# SCH_Robo_2025-09-25.net
KiCad netlist of a schematic drawn in EasyEDA
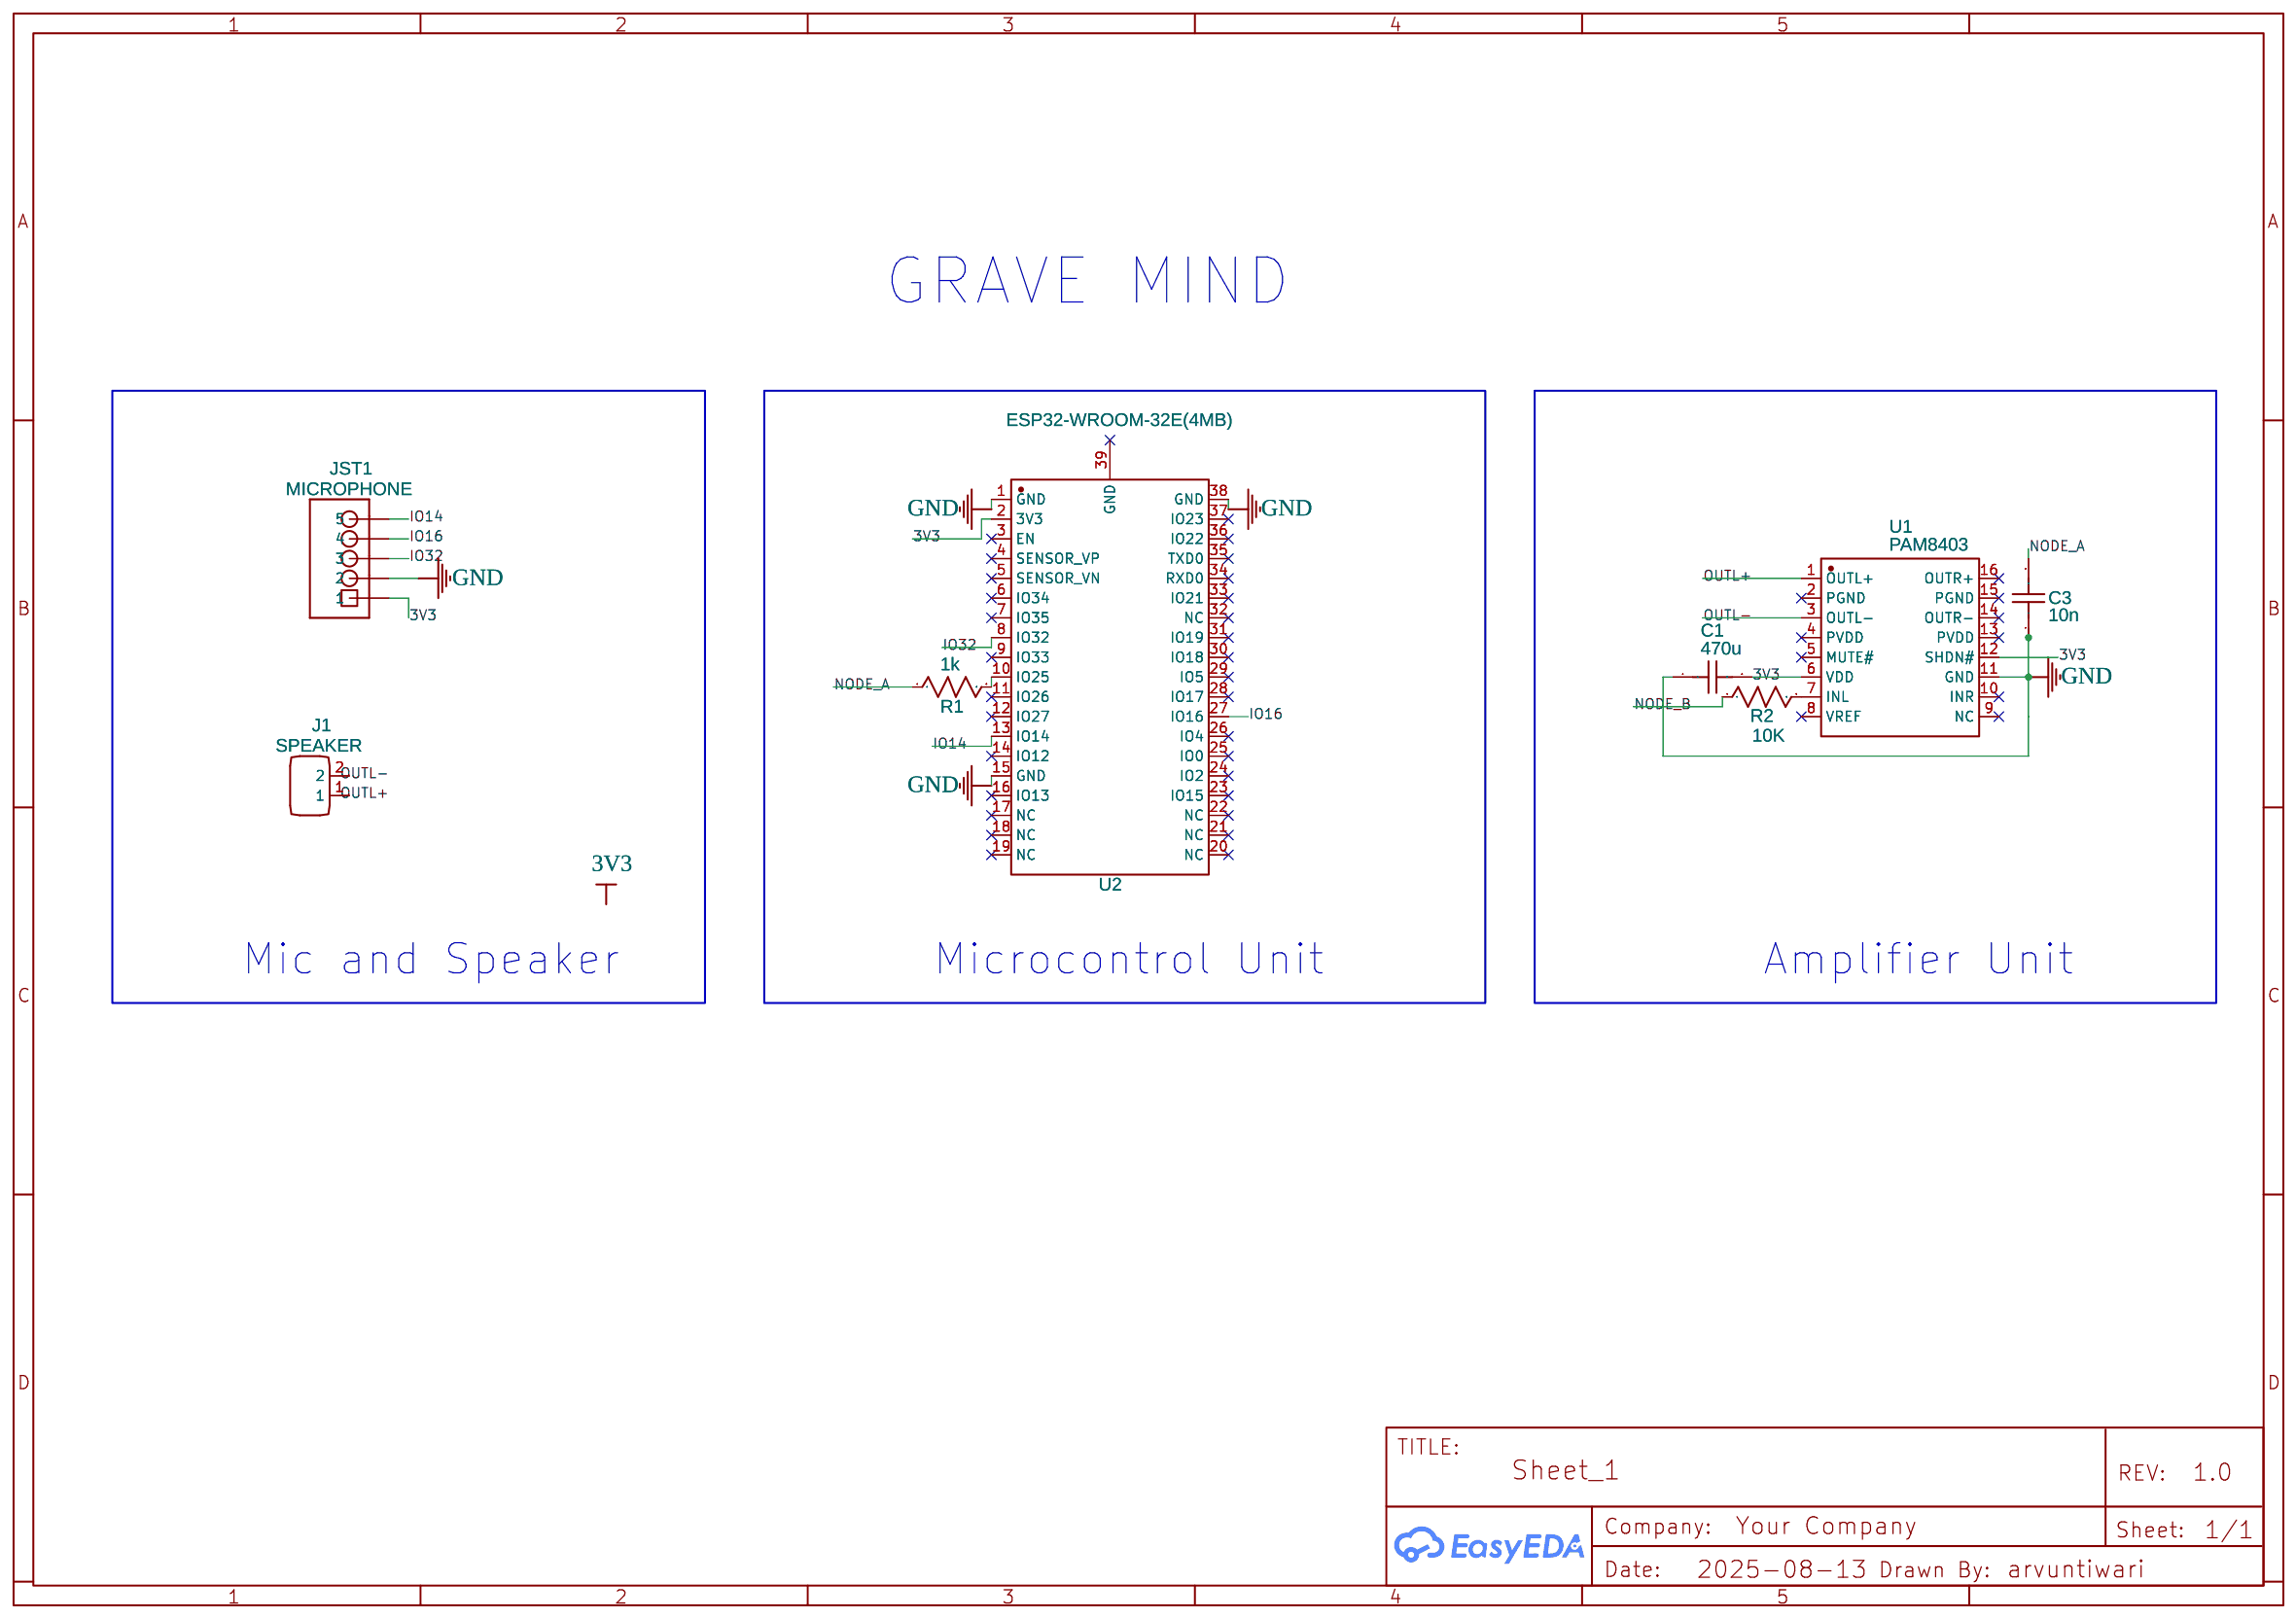
[diagram p0: schematic sheet]

(export (version "E")
  (design (tool "Eeschema 10.0.6"))
  (components
    (comp (ref "C1") (value "470u") (libsource (lib "") (part "C_0603_US_1")))
    (comp (ref "C3") (value "10n") (libsource (lib "") (part "C_0603_US")))
    (comp (ref "J1") (value "SPEAKER") (libsource (lib "") (part "JST 2pin Female")))
    (comp (ref "JST1") (value "MICROPHONE") (libsource (lib "") (part "JST_5-PIN_Female_Connector")))
    (comp (ref "R1") (value "1k") (libsource (lib "") (part "R_0603_US")))
    (comp (ref "R2") (value "10K") (libsource (lib "") (part "R_0603_US")))
    (comp (ref "U1")
      (value "PAM8403")
      (fields (field (name "Manufacturer") "Slkor(萨科微)"))
      (libsource (lib "") (part "PAM8403"))
    )
    (comp (ref "U2")
      (value "ESP32-WROOM-32E(4MB)")
      (fields
        (field (name "Manufacturer Part") "ESP32-WROOM-32E-N4")
        (field (name "Manufacturer") "ESPRESSIF(乐鑫)")
      )
      (libsource (lib "") (part "ESP32-WROOM-32E(4MB)"))
    )
  )
  (nets
    (net (code "1") (name "/IO14") (class "Default")
      (node (ref "JST1") (pin "5") (pinfunction "5_5") (pintype "unspecified"))
      (node (ref "U2") (pin "13") (pinfunction "IO14_13") (pintype "unspecified"))
    )
    (net (code "2") (name "/IO16") (class "Default")
      (node (ref "JST1") (pin "4") (pinfunction "4_4") (pintype "unspecified"))
      (node (ref "U2") (pin "27") (pinfunction "IO16_27") (pintype "unspecified"))
    )
    (net (code "3") (name "/IO32") (class "Default")
      (node (ref "JST1") (pin "3") (pinfunction "3_3") (pintype "unspecified"))
      (node (ref "U2") (pin "8") (pinfunction "IO32_8") (pintype "unspecified"))
    )
    (net (code "4") (name "/NODE_A") (class "Default")
      (node (ref "C3") (pin "2") (pinfunction "2_2") (pintype "unspecified"))
      (node (ref "R1") (pin "1") (pinfunction "1_1") (pintype "unspecified"))
    )
    (net (code "5") (name "/NODE_B") (class "Default")
      (node (ref "R2") (pin "1") (pinfunction "1_1") (pintype "unspecified"))
    )
    (net (code "6") (name "/OUTL+") (class "Default")
      (node (ref "J1") (pin "1") (pinfunction "1_1") (pintype "unspecified"))
      (node (ref "U1") (pin "1") (pinfunction "OUTL+_1") (pintype "unspecified"))
    )
    (net (code "7") (name "/OUTL-") (class "Default")
      (node (ref "J1") (pin "2") (pinfunction "2_2") (pintype "unspecified"))
      (node (ref "U1") (pin "3") (pinfunction "OUTL-_3") (pintype "unspecified"))
    )
    (net (code "8") (name "3V3") (class "Default")
      (node (ref "C1") (pin "2") (pinfunction "2_2") (pintype "unspecified"))
      (node (ref "JST1") (pin "1") (pinfunction "1_1") (pintype "unspecified"))
      (node (ref "U1") (pin "12") (pinfunction "SHDN#_12") (pintype "unspecified"))
      (node (ref "U1") (pin "6") (pinfunction "VDD_6") (pintype "unspecified"))
      (node (ref "U2") (pin "2") (pinfunction "3V3_2") (pintype "unspecified"))
    )
    (net (code "9") (name "GND") (class "Default")
      (node (ref "C1") (pin "1") (pinfunction "1_1") (pintype "unspecified"))
      (node (ref "C3") (pin "1") (pinfunction "1_1") (pintype "unspecified"))
      (node (ref "JST1") (pin "2") (pinfunction "2_2") (pintype "unspecified"))
      (node (ref "U1") (pin "11") (pinfunction "GND_11") (pintype "unspecified"))
      (node (ref "U2") (pin "1") (pinfunction "GND_1") (pintype "unspecified"))
      (node (ref "U2") (pin "15") (pinfunction "GND_15") (pintype "unspecified"))
      (node (ref "U2") (pin "38") (pinfunction "GND_38") (pintype "unspecified"))
    )
    (net (code "10") (name "Net-(U1-INL)") (class "Default")
      (node (ref "R2") (pin "2") (pinfunction "2_2") (pintype "unspecified"))
      (node (ref "U1") (pin "7") (pinfunction "INL_7") (pintype "unspecified"))
    )
    (net (code "11") (name "Net-(U2-IO25)") (class "Default")
      (node (ref "R1") (pin "2") (pinfunction "2_2") (pintype "unspecified"))
      (node (ref "U2") (pin "10") (pinfunction "IO25_10") (pintype "unspecified"))
    )
    (net (code "12") (name "unconnected-(U1-INR-Pad10)") (class "Default")
      (node (ref "U1") (pin "10") (pinfunction "INR_10") (pintype "unspecified+no_connect"))
    )
    (net (code "13") (name "unconnected-(U1-MUTE#-Pad5)") (class "Default")
      (node (ref "U1") (pin "5") (pinfunction "MUTE#_5") (pintype "unspecified+no_connect"))
    )
    (net (code "14") (name "unconnected-(U1-NC-Pad9)") (class "Default")
      (node (ref "U1") (pin "9") (pinfunction "NC_9") (pintype "unspecified+no_connect"))
    )
    (net (code "15") (name "unconnected-(U1-OUTR+-Pad16)") (class "Default")
      (node (ref "U1") (pin "16") (pinfunction "OUTR+_16") (pintype "unspecified+no_connect"))
    )
    (net (code "16") (name "unconnected-(U1-OUTR--Pad14)") (class "Default")
      (node (ref "U1") (pin "14") (pinfunction "OUTR-_14") (pintype "unspecified+no_connect"))
    )
    (net (code "17") (name "unconnected-(U1-PGND-Pad2)") (class "Default")
      (node (ref "U1") (pin "2") (pinfunction "PGND_2") (pintype "unspecified+no_connect"))
    )
    (net (code "18") (name "unconnected-(U1-PGND-Pad15)") (class "Default")
      (node (ref "U1") (pin "15") (pinfunction "PGND_15") (pintype "unspecified+no_connect"))
    )
    (net (code "19") (name "unconnected-(U1-PVDD-Pad4)") (class "Default")
      (node (ref "U1") (pin "4") (pinfunction "PVDD_4") (pintype "unspecified+no_connect"))
    )
    (net (code "20") (name "unconnected-(U1-PVDD-Pad13)") (class "Default")
      (node (ref "U1") (pin "13") (pinfunction "PVDD_13") (pintype "unspecified+no_connect"))
    )
    (net (code "21") (name "unconnected-(U1-VREF-Pad8)") (class "Default")
      (node (ref "U1") (pin "8") (pinfunction "VREF_8") (pintype "unspecified+no_connect"))
    )
    (net (code "22") (name "unconnected-(U2-EN-Pad3)") (class "Default")
      (node (ref "U2") (pin "3") (pinfunction "EN_3") (pintype "unspecified+no_connect"))
    )
    (net (code "23") (name "unconnected-(U2-GND-Pad39)") (class "Default")
      (node (ref "U2") (pin "39") (pinfunction "GND_39") (pintype "unspecified+no_connect"))
    )
    (net (code "24") (name "unconnected-(U2-IO0-Pad25)") (class "Default")
      (node (ref "U2") (pin "25") (pinfunction "IO0_25") (pintype "unspecified+no_connect"))
    )
    (net (code "25") (name "unconnected-(U2-IO2-Pad24)") (class "Default")
      (node (ref "U2") (pin "24") (pinfunction "IO2_24") (pintype "unspecified+no_connect"))
    )
    (net (code "26") (name "unconnected-(U2-IO4-Pad26)") (class "Default")
      (node (ref "U2") (pin "26") (pinfunction "IO4_26") (pintype "unspecified+no_connect"))
    )
    (net (code "27") (name "unconnected-(U2-IO5-Pad29)") (class "Default")
      (node (ref "U2") (pin "29") (pinfunction "IO5_29") (pintype "unspecified+no_connect"))
    )
    (net (code "28") (name "unconnected-(U2-IO12-Pad14)") (class "Default")
      (node (ref "U2") (pin "14") (pinfunction "IO12_14") (pintype "unspecified+no_connect"))
    )
    (net (code "29") (name "unconnected-(U2-IO13-Pad16)") (class "Default")
      (node (ref "U2") (pin "16") (pinfunction "IO13_16") (pintype "unspecified+no_connect"))
    )
    (net (code "30") (name "unconnected-(U2-IO15-Pad23)") (class "Default")
      (node (ref "U2") (pin "23") (pinfunction "IO15_23") (pintype "unspecified+no_connect"))
    )
    (net (code "31") (name "unconnected-(U2-IO17-Pad28)") (class "Default")
      (node (ref "U2") (pin "28") (pinfunction "IO17_28") (pintype "unspecified+no_connect"))
    )
    (net (code "32") (name "unconnected-(U2-IO18-Pad30)") (class "Default")
      (node (ref "U2") (pin "30") (pinfunction "IO18_30") (pintype "unspecified+no_connect"))
    )
    (net (code "33") (name "unconnected-(U2-IO19-Pad31)") (class "Default")
      (node (ref "U2") (pin "31") (pinfunction "IO19_31") (pintype "unspecified+no_connect"))
    )
    (net (code "34") (name "unconnected-(U2-IO21-Pad33)") (class "Default")
      (node (ref "U2") (pin "33") (pinfunction "IO21_33") (pintype "unspecified+no_connect"))
    )
    (net (code "35") (name "unconnected-(U2-IO22-Pad36)") (class "Default")
      (node (ref "U2") (pin "36") (pinfunction "IO22_36") (pintype "unspecified+no_connect"))
    )
    (net (code "36") (name "unconnected-(U2-IO23-Pad37)") (class "Default")
      (node (ref "U2") (pin "37") (pinfunction "IO23_37") (pintype "unspecified+no_connect"))
    )
    (net (code "37") (name "unconnected-(U2-IO26-Pad11)") (class "Default")
      (node (ref "U2") (pin "11") (pinfunction "IO26_11") (pintype "unspecified+no_connect"))
    )
    (net (code "38") (name "unconnected-(U2-IO27-Pad12)") (class "Default")
      (node (ref "U2") (pin "12") (pinfunction "IO27_12") (pintype "unspecified+no_connect"))
    )
    (net (code "39") (name "unconnected-(U2-IO33-Pad9)") (class "Default")
      (node (ref "U2") (pin "9") (pinfunction "IO33_9") (pintype "unspecified+no_connect"))
    )
    (net (code "40") (name "unconnected-(U2-IO34-Pad6)") (class "Default")
      (node (ref "U2") (pin "6") (pinfunction "IO34_6") (pintype "unspecified+no_connect"))
    )
    (net (code "41") (name "unconnected-(U2-IO35-Pad7)") (class "Default")
      (node (ref "U2") (pin "7") (pinfunction "IO35_7") (pintype "unspecified+no_connect"))
    )
    (net (code "42") (name "unconnected-(U2-NC-Pad17)") (class "Default")
      (node (ref "U2") (pin "17") (pinfunction "NC_17") (pintype "unspecified+no_connect"))
    )
    (net (code "43") (name "unconnected-(U2-NC-Pad18)") (class "Default")
      (node (ref "U2") (pin "18") (pinfunction "NC_18") (pintype "unspecified+no_connect"))
    )
    (net (code "44") (name "unconnected-(U2-NC-Pad19)") (class "Default")
      (node (ref "U2") (pin "19") (pinfunction "NC_19") (pintype "unspecified+no_connect"))
    )
    (net (code "45") (name "unconnected-(U2-NC-Pad20)") (class "Default")
      (node (ref "U2") (pin "20") (pinfunction "NC_20") (pintype "unspecified+no_connect"))
    )
    (net (code "46") (name "unconnected-(U2-NC-Pad21)") (class "Default")
      (node (ref "U2") (pin "21") (pinfunction "NC_21") (pintype "unspecified+no_connect"))
    )
    (net (code "47") (name "unconnected-(U2-NC-Pad22)") (class "Default")
      (node (ref "U2") (pin "22") (pinfunction "NC_22") (pintype "unspecified+no_connect"))
    )
    (net (code "48") (name "unconnected-(U2-NC-Pad32)") (class "Default")
      (node (ref "U2") (pin "32") (pinfunction "NC_32") (pintype "unspecified+no_connect"))
    )
    (net (code "49") (name "unconnected-(U2-RXD0-Pad34)") (class "Default")
      (node (ref "U2") (pin "34") (pinfunction "RXD0_34") (pintype "unspecified+no_connect"))
    )
    (net (code "50") (name "unconnected-(U2-SENSOR_VN-Pad5)") (class "Default")
      (node (ref "U2") (pin "5") (pinfunction "SENSOR_VN_5") (pintype "unspecified+no_connect"))
    )
    (net (code "51") (name "unconnected-(U2-SENSOR_VP-Pad4)") (class "Default")
      (node (ref "U2") (pin "4") (pinfunction "SENSOR_VP_4") (pintype "unspecified+no_connect"))
    )
    (net (code "52") (name "unconnected-(U2-TXD0-Pad35)") (class "Default")
      (node (ref "U2") (pin "35") (pinfunction "TXD0_35") (pintype "unspecified+no_connect"))
    )
  )
)
